# 5VAC-DC.net
KiCad netlist of a schematic drawn in EAGLE
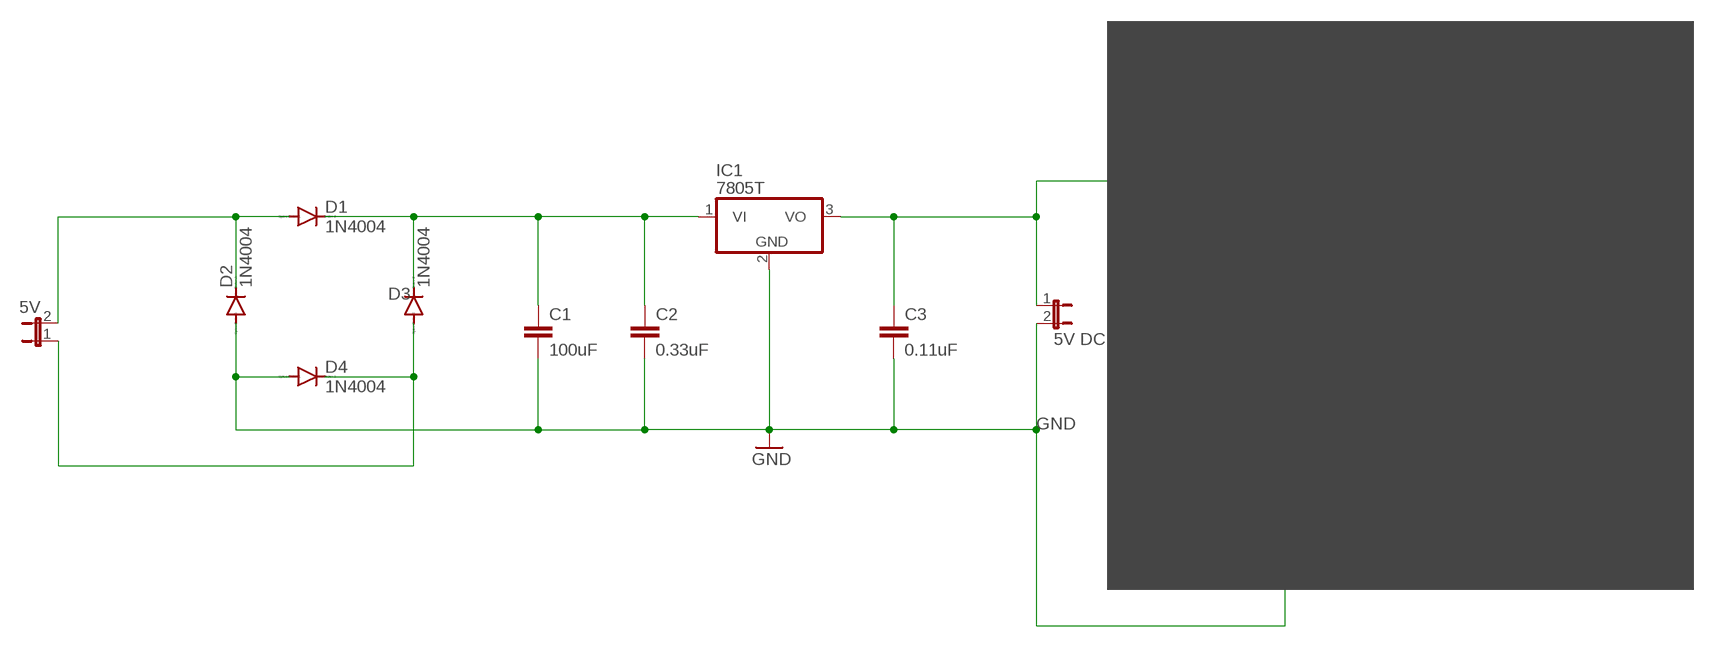
[diagram p0: schematic, sheet 1]

(export (version "E")
  (design (tool "Eeschema 10.0.6"))
  (components
    (comp (ref "C1")
      (value "100uF")
      (footprint "eagle-import:C2.5-3")
      (libsource (lib "eagle-import") (part "C2,5-3"))
    )
    (comp (ref "C2")
      (value "0.33uF")
      (footprint "eagle-import:C2.5-3")
      (libsource (lib "eagle-import") (part "C2,5-3"))
    )
    (comp (ref "C3")
      (value "0.11uF")
      (footprint "eagle-import:C2.5-3")
      (libsource (lib "eagle-import") (part "C2,5-3"))
    )
    (comp (ref "D1")
      (value "1N4004")
      (footprint "eagle-import:DO41-10")
      (libsource (lib "eagle-import") (part "1N4004"))
    )
    (comp (ref "D2")
      (value "1N4004")
      (footprint "eagle-import:DO41-10")
      (libsource (lib "eagle-import") (part "1N4004"))
    )
    (comp (ref "D3")
      (value "1N4004")
      (footprint "eagle-import:DO41-10")
      (libsource (lib "eagle-import") (part "1N4004"))
    )
    (comp (ref "D4")
      (value "1N4004")
      (footprint "eagle-import:DO41-10")
      (libsource (lib "eagle-import") (part "1N4004"))
    )
    (comp (ref "I/P")
      (value "5V")
      (footprint "eagle-import:JP1")
      (libsource (lib "eagle-import") (part "JP1E"))
    )
    (comp (ref "IC1")
      (value "7805T")
      (footprint "eagle-import:TO220H")
      (libsource (lib "eagle-import") (part "78T05"))
    )
    (comp (ref "JP2")
      (value "5V DC")
      (footprint "eagle-import:JP1")
      (libsource (lib "eagle-import") (part "JP1E"))
    )
    (comp (ref "U$1")
      (value "MEGA8L-DEV")
      (footprint "eagle-import:TQFP-MEGA8")
      (libsource (lib "eagle-import") (part "MEGA8L-DEV"))
    )
  )
  (nets
    (net (code "1") (name "GND") (class "Default")
      (node (ref "C1") (pin "2") (pinfunction "2_2") (pintype "passive"))
      (node (ref "C2") (pin "2") (pinfunction "2_2") (pintype "passive"))
      (node (ref "C3") (pin "2") (pinfunction "2_2") (pintype "passive"))
      (node (ref "D2") (pin "A") (pinfunction "A_A") (pintype "passive"))
      (node (ref "D4") (pin "A") (pinfunction "A_A") (pintype "passive"))
      (node (ref "IC1") (pin "2") (pinfunction "GND_2") (pintype "passive"))
      (node (ref "JP2") (pin "2") (pinfunction "2_2") (pintype "passive"))
      (node (ref "U$1") (pin "P$9") (pinfunction "P$9_P$9") (pintype "bidirectional"))
    )
    (net (code "2") (name "Net-(D1-PadA)") (class "Default")
      (node (ref "D1") (pin "A") (pinfunction "A_A") (pintype "passive"))
      (node (ref "D2") (pin "C") (pinfunction "C_C") (pintype "passive"))
      (node (ref "I/P") (pin "2") (pinfunction "2_2") (pintype "passive"))
    )
    (net (code "3") (name "Net-(D3-PadA)") (class "Default")
      (node (ref "D3") (pin "A") (pinfunction "A_A") (pintype "passive"))
      (node (ref "D4") (pin "C") (pinfunction "C_C") (pintype "passive"))
      (node (ref "I/P") (pin "1") (pinfunction "1_1") (pintype "passive"))
    )
    (net (code "4") (name "Net-(IC1-VI)") (class "Default")
      (node (ref "C1") (pin "1") (pinfunction "1_1") (pintype "passive"))
      (node (ref "C2") (pin "1") (pinfunction "1_1") (pintype "passive"))
      (node (ref "D1") (pin "C") (pinfunction "C_C") (pintype "passive"))
      (node (ref "D3") (pin "C") (pinfunction "C_C") (pintype "passive"))
      (node (ref "IC1") (pin "1") (pinfunction "VI_1") (pintype "input"))
    )
    (net (code "5") (name "Net-(IC1-VO)") (class "Default")
      (node (ref "C3") (pin "1") (pinfunction "1_1") (pintype "passive"))
      (node (ref "IC1") (pin "3") (pinfunction "VO_3") (pintype "passive"))
      (node (ref "JP2") (pin "1") (pinfunction "1_1") (pintype "passive"))
      (node (ref "U$1") (pin "P$1") (pinfunction "P$1_P$1") (pintype "bidirectional"))
    )
    (net (code "6") (name "unconnected-(U$1-PadP$2)") (class "Default")
      (node (ref "U$1") (pin "P$2") (pinfunction "P$2_P$2") (pintype "bidirectional"))
    )
    (net (code "7") (name "unconnected-(U$1-PadP$3)") (class "Default")
      (node (ref "U$1") (pin "P$3") (pinfunction "P$3_P$3") (pintype "bidirectional"))
    )
    (net (code "8") (name "unconnected-(U$1-PadP$4)") (class "Default")
      (node (ref "U$1") (pin "P$4") (pinfunction "P$4_P$4") (pintype "bidirectional"))
    )
    (net (code "9") (name "unconnected-(U$1-PadP$5)") (class "Default")
      (node (ref "U$1") (pin "P$5") (pinfunction "P$5_P$5") (pintype "bidirectional"))
    )
    (net (code "10") (name "unconnected-(U$1-PadP$6)") (class "Default")
      (node (ref "U$1") (pin "P$6") (pinfunction "P$6_P$6") (pintype "bidirectional"))
    )
    (net (code "11") (name "unconnected-(U$1-PadP$7)") (class "Default")
      (node (ref "U$1") (pin "P$7") (pinfunction "P$7_P$7") (pintype "bidirectional"))
    )
    (net (code "12") (name "unconnected-(U$1-PadP$8)") (class "Default")
      (node (ref "U$1") (pin "P$8") (pinfunction "P$8_P$8") (pintype "bidirectional"))
    )
    (net (code "13") (name "unconnected-(U$1-PadP$10)") (class "Default")
      (node (ref "U$1") (pin "P$10") (pinfunction "P$10_P$10") (pintype "bidirectional"))
    )
    (net (code "14") (name "unconnected-(U$1-PadP$11)") (class "Default")
      (node (ref "U$1") (pin "P$11") (pinfunction "P$11_P$11") (pintype "bidirectional"))
    )
    (net (code "15") (name "unconnected-(U$1-PadP$12)") (class "Default")
      (node (ref "U$1") (pin "P$12") (pinfunction "P$12_P$12") (pintype "bidirectional"))
    )
    (net (code "16") (name "unconnected-(U$1-PadP$13)") (class "Default")
      (node (ref "U$1") (pin "P$13") (pinfunction "P$13_P$13") (pintype "bidirectional"))
    )
    (net (code "17") (name "unconnected-(U$1-PadP$14)") (class "Default")
      (node (ref "U$1") (pin "P$14") (pinfunction "P$14_P$14") (pintype "bidirectional"))
    )
    (net (code "18") (name "unconnected-(U$1-PadP$15)") (class "Default")
      (node (ref "U$1") (pin "P$15") (pinfunction "P$15_P$15") (pintype "bidirectional"))
    )
    (net (code "19") (name "unconnected-(U$1-PadP$16)") (class "Default")
      (node (ref "U$1") (pin "P$16") (pinfunction "P$16_P$16") (pintype "bidirectional"))
    )
    (net (code "20") (name "unconnected-(U$1-PadP$17)") (class "Default")
      (node (ref "U$1") (pin "P$17") (pinfunction "P$17_P$17") (pintype "bidirectional"))
    )
    (net (code "21") (name "unconnected-(U$1-PadP$18)") (class "Default")
      (node (ref "U$1") (pin "P$18") (pinfunction "P$18_P$18") (pintype "bidirectional"))
    )
    (net (code "22") (name "unconnected-(U$1-PadP$19)") (class "Default")
      (node (ref "U$1") (pin "P$19") (pinfunction "P$19_P$19") (pintype "bidirectional"))
    )
    (net (code "23") (name "unconnected-(U$1-PadP$20)") (class "Default")
      (node (ref "U$1") (pin "P$20") (pinfunction "P$20_P$20") (pintype "bidirectional"))
    )
    (net (code "24") (name "unconnected-(U$1-PadP$21)") (class "Default")
      (node (ref "U$1") (pin "P$21") (pinfunction "P$21_P$21") (pintype "bidirectional"))
    )
    (net (code "25") (name "unconnected-(U$1-PadP$22)") (class "Default")
      (node (ref "U$1") (pin "P$22") (pinfunction "P$22_P$22") (pintype "bidirectional"))
    )
    (net (code "26") (name "unconnected-(U$1-PadP$23)") (class "Default")
      (node (ref "U$1") (pin "P$23") (pinfunction "P$23_P$23") (pintype "bidirectional"))
    )
    (net (code "27") (name "unconnected-(U$1-PadP$24)") (class "Default")
      (node (ref "U$1") (pin "P$24") (pinfunction "P$24_P$24") (pintype "bidirectional"))
    )
    (net (code "28") (name "unconnected-(U$1-PadP$25)") (class "Default")
      (node (ref "U$1") (pin "P$25") (pinfunction "P$25_P$25") (pintype "bidirectional"))
    )
    (net (code "29") (name "unconnected-(U$1-PadP$26)") (class "Default")
      (node (ref "U$1") (pin "P$26") (pinfunction "P$26_P$26") (pintype "bidirectional"))
    )
    (net (code "30") (name "unconnected-(U$1-PadP$27)") (class "Default")
      (node (ref "U$1") (pin "P$27") (pinfunction "P$27_P$27") (pintype "bidirectional"))
    )
    (net (code "31") (name "unconnected-(U$1-PadP$28)") (class "Default")
      (node (ref "U$1") (pin "P$28") (pinfunction "P$28_P$28") (pintype "bidirectional"))
    )
    (net (code "32") (name "unconnected-(U$1-PadP$29)") (class "Default")
      (node (ref "U$1") (pin "P$29") (pinfunction "P$29_P$29") (pintype "bidirectional"))
    )
    (net (code "33") (name "unconnected-(U$1-PadP$30)") (class "Default")
      (node (ref "U$1") (pin "P$30") (pinfunction "P$30_P$30") (pintype "bidirectional"))
    )
    (net (code "34") (name "unconnected-(U$1-PadP$31)") (class "Default")
      (node (ref "U$1") (pin "P$31") (pinfunction "P$31_P$31") (pintype "bidirectional"))
    )
    (net (code "35") (name "unconnected-(U$1-PadP$32)") (class "Default")
      (node (ref "U$1") (pin "P$32") (pinfunction "P$32_P$32") (pintype "bidirectional"))
    )
  )
)
